# PenguinPi.net
KiCad netlist of a schematic drawn in Altium Designer
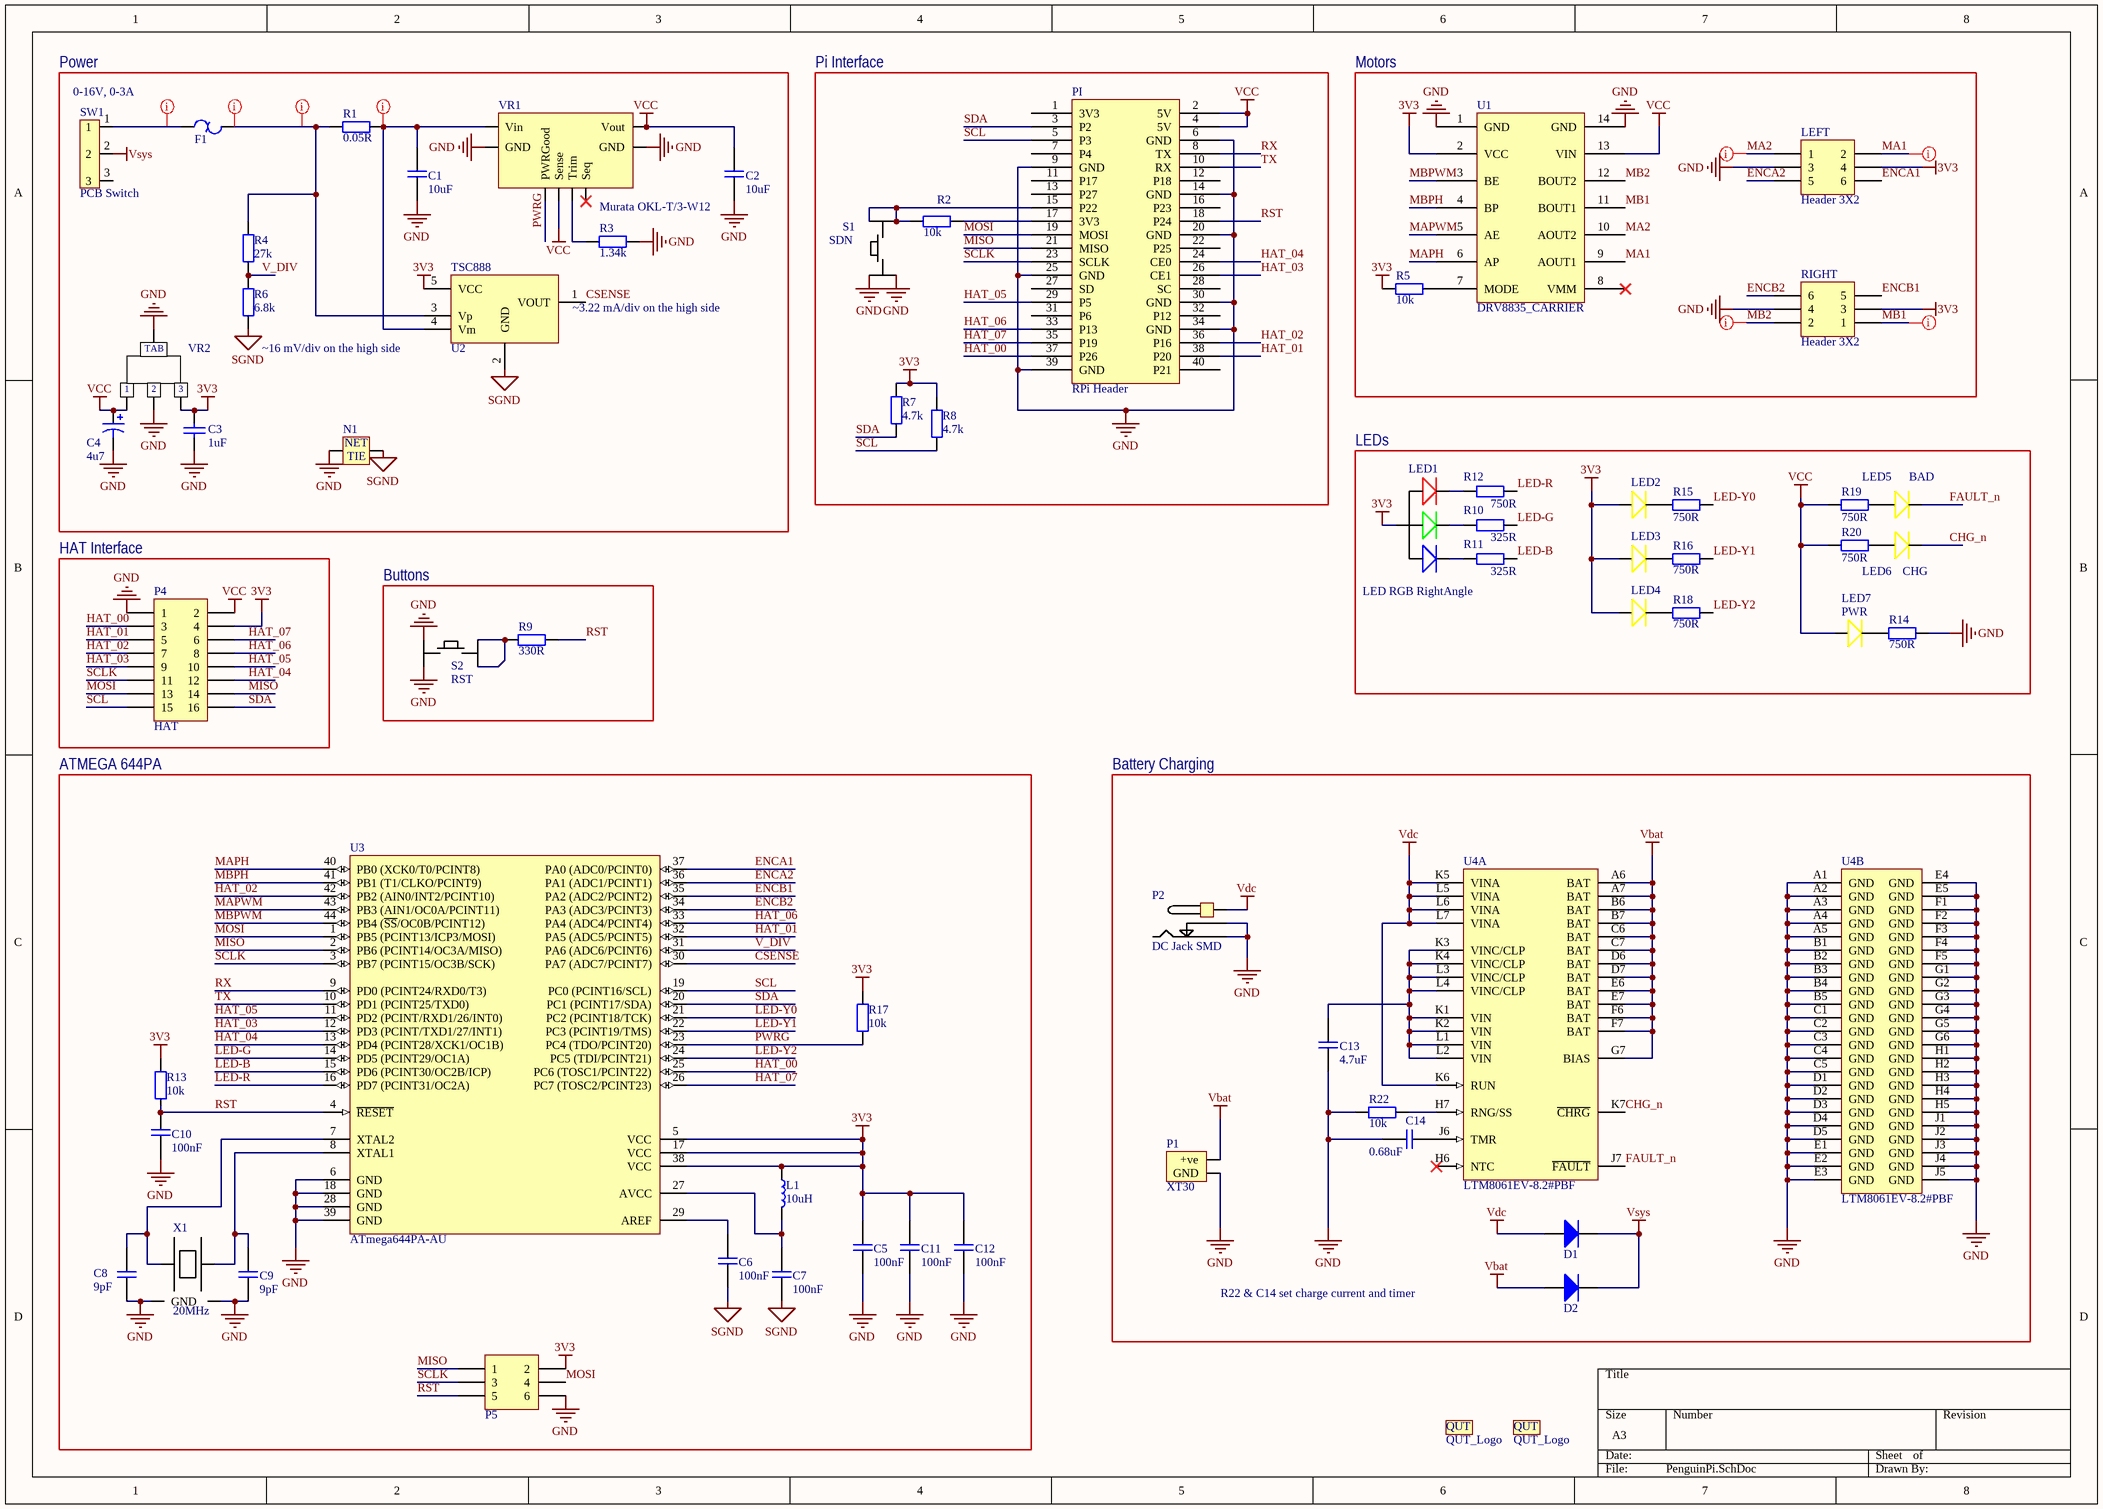
[diagram p0: PenguinPi.SchDoc]

(export (version "E")
  (design (tool "Eeschema 10.0.6"))
  (components
    (comp (ref "C1")
      (value "10uF")
      (footprint "CAPC2012X07N")
      (description "Surface mount capacitor")
      (fields (field (name "Comment") "CAP SMD"))
      (libsource (lib "Penguin") (part "CAP SMD"))
    )
    (comp (ref "C2")
      (value "10uF")
      (footprint "CAPC2012X07N")
      (description "Surface mount capacitor")
      (fields (field (name "Comment") "CAP SMD"))
      (libsource (lib "Penguin") (part "CAP SMD"))
    )
    (comp (ref "C3")
      (value "1uF")
      (footprint "6-0805_M")
      (description "Capacitor")
      (fields (field (name "Comment") "Cap") (field (name "PUBLISHER") "Altium Limited"))
      (libsource (lib "Miscellaneous Devices") (part "Cap"))
    )
    (comp (ref "C4")
      (value "4u7")
      (footprint "6-0805_M")
      (description "Polarized Capacitor (Radial)")
      (fields (field (name "Comment") "Cap Pol1") (field (name "PUBLISHER") "Altium Limited"))
      (libsource (lib "Miscellaneous Devices") (part "Cap Pol1"))
    )
    (comp (ref "C5")
      (value "100nF")
      (footprint "CAPC2012X07N")
      (description "Surface mount capacitor")
      (fields (field (name "Comment") "CAP SMD"))
      (libsource (lib "Penguin") (part "CAP SMD"))
    )
    (comp (ref "C6")
      (value "100nF")
      (footprint "CAPC2012X07N")
      (description "Surface mount capacitor")
      (fields (field (name "Comment") "CAP SMD"))
      (libsource (lib "Penguin") (part "CAP SMD"))
    )
    (comp (ref "C7")
      (value "100nF")
      (footprint "CAPC2012X07N")
      (description "Surface mount capacitor")
      (fields (field (name "Comment") "CAP SMD"))
      (libsource (lib "Penguin") (part "CAP SMD"))
    )
    (comp (ref "C8")
      (value "9pF")
      (footprint "CAPC2012X07N")
      (description "Surface mount capacitor")
      (fields (field (name "Comment") "CAP SMD"))
      (libsource (lib "Penguin") (part "CAP SMD"))
    )
    (comp (ref "C9")
      (value "9pF")
      (footprint "CAPC2012X07N")
      (description "Surface mount capacitor")
      (fields (field (name "Comment") "CAP SMD"))
      (libsource (lib "Penguin") (part "CAP SMD"))
    )
    (comp (ref "C10")
      (value "100nF")
      (footprint "CAPC2012X07N")
      (description "Surface mount capacitor")
      (fields (field (name "Comment") "CAP SMD"))
      (libsource (lib "Penguin") (part "CAP SMD"))
    )
    (comp (ref "C11")
      (value "100nF")
      (footprint "CAPC2012X07N")
      (description "Surface mount capacitor")
      (fields (field (name "Comment") "CAP SMD"))
      (libsource (lib "Penguin") (part "CAP SMD"))
    )
    (comp (ref "C12")
      (value "100nF")
      (footprint "CAPC2012X07N")
      (description "Surface mount capacitor")
      (fields (field (name "Comment") "CAP SMD"))
      (libsource (lib "Penguin") (part "CAP SMD"))
    )
    (comp (ref "C13")
      (value "4.7uF")
      (footprint "CAPC2012X07N")
      (description "Surface mount capacitor")
      (fields (field (name "Comment") "CAP SMD"))
      (libsource (lib "Penguin") (part "CAP SMD"))
    )
    (comp (ref "C14")
      (value "0.68uF")
      (footprint "CAPC2012X07N")
      (description "Surface mount capacitor")
      (fields (field (name "Comment") "CAP SMD"))
      (libsource (lib "Penguin") (part "CAP SMD"))
    )
    (comp (ref "D1")
      (value "SMD DIODE")
      (footprint "SODFL470X110-2N")
      (description "Surface mount Diode")
      (libsource (lib "Penguin") (part "SMD DIODE"))
    )
    (comp (ref "D2")
      (value "SMD DIODE")
      (footprint "SODFL470X110-2N")
      (description "Surface mount Diode")
      (libsource (lib "Penguin") (part "SMD DIODE"))
    )
    (comp (ref "F1")
      (value "RGEF250")
      (footprint "MF-MSMF250/16X-2")
      (description "PPTC Thermal Fuse")
      (libsource (lib "Penguin") (part "RGEF250"))
    )
    (comp (ref "L1")
      (value "10uH")
      (footprint "CM322522")
      (description "Surface Mount Inductor - varying sizes")
      (fields (field (name "Comment") "INDUCTOR SMD"))
      (libsource (lib "Penguin") (part "INDUCTOR SMD"))
    )
    (comp (ref "LED1")
      (value "LED RGB RightAngle")
      (footprint "LED RGB RightAngle")
      (libsource (lib "PenguinPi_v2") (part "LED RGB RightAngle"))
    )
    (comp (ref "LED2")
      (value "~")
      (footprint "LED YELLOW RightAngle")
      (libsource (lib "PenguinPi_v2") (part "LED Yellow RightAngle"))
    )
    (comp (ref "LED3")
      (value "~")
      (footprint "LED YELLOW RightAngle")
      (libsource (lib "PenguinPi_v2") (part "LED Yellow RightAngle"))
    )
    (comp (ref "LED4")
      (value "~")
      (footprint "LED YELLOW RightAngle")
      (libsource (lib "PenguinPi_v2") (part "LED Yellow RightAngle"))
    )
    (comp (ref "LED5")
      (value "BAD")
      (footprint "RESC2012X07N")
      (libsource (lib "PenguinPi_v2") (part "LED Yellow RightAngle"))
    )
    (comp (ref "LED6")
      (value "CHG")
      (footprint "RESC2012X07N")
      (libsource (lib "PenguinPi_v2") (part "LED Yellow RightAngle"))
    )
    (comp (ref "LED7")
      (value "PWR")
      (footprint "LED YELLOW RightAngle")
      (libsource (lib "PenguinPi_v2") (part "LED Yellow RightAngle"))
    )
    (comp (ref "LEFT")
      (value "Header 3X2")
      (footprint "HDR2X3")
      (description "Header, 3-Pin, Dual row")
      (fields (field (name "PUBLISHER") "Altium Limited"))
      (libsource (lib "") (part "Header 3X2_1"))
    )
    (comp (ref "LG1") (value "QUT_Logo") (footprint "QUT_Logo") (libsource (lib "Penguin") (part "QUT_Logo")))
    (comp (ref "LG2") (value "QUT_Logo") (footprint "QUT_Logo") (libsource (lib "Penguin") (part "QUT_Logo")))
    (comp (ref "N1")
      (value "NETTIE")
      (footprint "NETTIE-SMD-5mil")
      (libsource (lib "Penguin") (part "NETTIE"))
    )
    (comp (ref "P1") (value "XT30") (footprint "XT30 - PCB mount") (libsource (lib "QUT") (part "XT30")))
    (comp (ref "P2")
      (value "DC Jack SMD")
      (footprint "DC Jack SMD")
      (libsource (lib "QUT") (part "DC Jack SMD"))
    )
    (comp (ref "P4")
      (value "HAT")
      (footprint "HDR2X8")
      (description "Header, 8-Pin, Dual row")
      (fields (field (name "PUBLISHER") "Altium Limited"))
      (libsource (lib "Miscellaneous Connectors") (part "Header 8X2"))
    )
    (comp (ref "P5")
      (value "ISP")
      (footprint "Header 3x2 nonstandard")
      (description "3 by 2 header, staggered pin arrangement")
      (libsource (lib "Penguin") (part "Header 3x2 Staggered"))
    )
    (comp (ref "PI")
      (value "RPi Header")
      (footprint "RPI 2 Header")
      (description "GPIO connector for Raspberry Pi Microcomputer")
      (libsource (lib "Penguin") (part "RPi 2 Header"))
    )
    (comp (ref "R1")
      (value "0.05R")
      (footprint "RESC3216X06M")
      (description "0805 surface mount resistor")
      (fields (field (name "Comment") "RES SMD"))
      (libsource (lib "") (part "RES SMD_3"))
    )
    (comp (ref "R2")
      (value "10k")
      (footprint "RESC2012X07N")
      (description "0805 surface mount resistor")
      (fields (field (name "Comment") "RES SMD"))
      (libsource (lib "Penguin") (part "RES SMD"))
    )
    (comp (ref "R3")
      (value "1.34k")
      (footprint "RESC2012X07N")
      (description "0805 surface mount resistor")
      (fields (field (name "Comment") "RES SMD"))
      (libsource (lib "") (part "RES SMD_2"))
    )
    (comp (ref "R4")
      (value "27k")
      (footprint "RESC2012X07N")
      (description "0805 surface mount resistor")
      (fields (field (name "Comment") "RES SMD"))
      (libsource (lib "") (part "RES SMD_1"))
    )
    (comp (ref "R5")
      (value "10k")
      (footprint "RESC2012X07N")
      (description "0805 surface mount resistor")
      (fields (field (name "Comment") "RES SMD"))
      (libsource (lib "Penguin") (part "RES SMD"))
    )
    (comp (ref "R6")
      (value "6.8k")
      (footprint "RESC2012X07N")
      (description "0805 surface mount resistor")
      (fields (field (name "Comment") "RES SMD"))
      (libsource (lib "") (part "RES SMD_1"))
    )
    (comp (ref "R7")
      (value "4.7k")
      (footprint "RESC2012X07N")
      (description "0805 surface mount resistor")
      (fields (field (name "Comment") "RES SMD"))
      (libsource (lib "") (part "RES SMD_1"))
    )
    (comp (ref "R8")
      (value "4.7k")
      (footprint "RESC2012X07N")
      (description "0805 surface mount resistor")
      (fields (field (name "Comment") "RES SMD"))
      (libsource (lib "") (part "RES SMD_1"))
    )
    (comp (ref "R9")
      (value "330R")
      (footprint "RESC2012X07N")
      (description "0805 surface mount resistor")
      (fields (field (name "Comment") "RES SMD"))
      (libsource (lib "Penguin") (part "RES SMD"))
    )
    (comp (ref "R10")
      (value "325R")
      (footprint "RESC2012X07N")
      (description "0805 surface mount resistor")
      (fields (field (name "Comment") "RES SMD"))
      (libsource (lib "Penguin") (part "RES SMD"))
    )
    (comp (ref "R11")
      (value "325R")
      (footprint "RESC2012X07N")
      (description "0805 surface mount resistor")
      (fields (field (name "Comment") "RES SMD"))
      (libsource (lib "Penguin") (part "RES SMD"))
    )
    (comp (ref "R12")
      (value "750R")
      (footprint "RESC2012X07N")
      (description "0805 surface mount resistor")
      (fields (field (name "Comment") "RES SMD"))
      (libsource (lib "Penguin") (part "RES SMD"))
    )
    (comp (ref "R13")
      (value "10k")
      (footprint "RESC2012X07N")
      (description "0805 surface mount resistor")
      (fields (field (name "Comment") "RES SMD"))
      (libsource (lib "") (part "RES SMD_1"))
    )
    (comp (ref "R14")
      (value "750R")
      (footprint "RESC2012X07N")
      (description "0805 surface mount resistor")
      (fields (field (name "Comment") "RES SMD"))
      (libsource (lib "Penguin") (part "RES SMD"))
    )
    (comp (ref "R15")
      (value "750R")
      (footprint "RESC2012X07N")
      (description "0805 surface mount resistor")
      (fields (field (name "Comment") "RES SMD"))
      (libsource (lib "Penguin") (part "RES SMD"))
    )
    (comp (ref "R16")
      (value "750R")
      (footprint "RESC2012X07N")
      (description "0805 surface mount resistor")
      (fields (field (name "Comment") "RES SMD"))
      (libsource (lib "Penguin") (part "RES SMD"))
    )
    (comp (ref "R17")
      (value "10k")
      (footprint "RESC2012X07N")
      (description "0805 surface mount resistor")
      (fields (field (name "Comment") "RES SMD"))
      (libsource (lib "") (part "RES SMD_1"))
    )
    (comp (ref "R18")
      (value "750R")
      (footprint "RESC2012X07N")
      (description "0805 surface mount resistor")
      (fields (field (name "Comment") "RES SMD"))
      (libsource (lib "Penguin") (part "RES SMD"))
    )
    (comp (ref "R19")
      (value "750R")
      (footprint "6-0805_M")
      (description "0805 surface mount resistor")
      (fields (field (name "Comment") "RES SMD"))
      (libsource (lib "Penguin") (part "RES SMD"))
    )
    (comp (ref "R20")
      (value "750R")
      (footprint "6-0805_M")
      (description "0805 surface mount resistor")
      (fields (field (name "Comment") "RES SMD"))
      (libsource (lib "Penguin") (part "RES SMD"))
    )
    (comp (ref "R22")
      (value "10k")
      (footprint "RESC2012X07N")
      (description "0805 surface mount resistor")
      (fields (field (name "Comment") "RES SMD"))
      (libsource (lib "") (part "RES SMD_2"))
    )
    (comp (ref "RIGHT")
      (value "Header 3X2")
      (footprint "HDR2X3")
      (description "Header, 3-Pin, Dual row")
      (fields (field (name "PUBLISHER") "Altium Limited"))
      (libsource (lib "Miscellaneous Connectors") (part "Header 3X2"))
    )
    (comp (ref "S1")
      (value "SDN")
      (footprint "E-SWITCH-TL3342")
      (description "TL 3342 surface mount pushbutton")
      (libsource (lib "Penguin") (part "E-SWITCH-PUSHBUTTON"))
    )
    (comp (ref "S2")
      (value "RST")
      (footprint "E-SWITCH-TL3342")
      (description "TL 3342 surface mount pushbutton")
      (libsource (lib "Penguin") (part "E-SWITCH-PUSHBUTTON"))
    )
    (comp (ref "SW1")
      (value "PCB Switch")
      (footprint "PCB Switch")
      (libsource (lib "PenguinPi_v2") (part "PCB Switch"))
    )
    (comp (ref "U1")
      (value "DRV8835_CARRIER")
      (footprint "DRV8835_CARRIER")
      (description "DRV8835 Motor Controller")
      (libsource (lib "Penguin") (part "DRV8835_CARRIER"))
    )
    (comp (ref "U2")
      (value "TSC888")
      (footprint "SOT95P280X145-5N")
      (description "Curent Sense Amplifier")
      (libsource (lib "Penguin") (part "TSC888"))
    )
    (comp (ref "U3")
      (value "ATmega644PA-AU")
      (footprint "44A_L")
      (libsource (lib "Altium Content Vault") (part "MC-8B-ATM128-SQ44"))
    )
    (comp (ref "U4")
      (value "LTM8061EV-8.2#PBF")
      (footprint "LT-LGA-77-05-08-1856_V")
      (description "32 V, 2 A uModule Li-Ion / Polymer Battery Charger, 77-pin LGA, -40 to 125 degC, Pb-Free, Tray")
      (fields (field (name "MANUFACTURER") "Linear Technology"))
      (libsource (lib "Altium Content Vault") (part "CMP-0483-00150-1"))
    )
    (comp (ref "VR1")
      (value "Murata OKL-T/3-W12")
      (footprint "OKL-T/3-W12")
      (libsource (lib "PenguinPi_v2") (part "Murata OKL-T/3-W12"))
    )
    (comp (ref "VR2") (value "FT_SOT223") (footprint "SOT233-4N") (libsource (lib "QUT") (part "FT_SOT223")))
    (comp (ref "X1") (value "20MHz") (footprint "XTAL TSX3225") (libsource (lib "QUT") (part "XTAL ABM3B")))
  )
  (nets
    (net (code "1") (name "/CHG_n") (class "Default")
      (node (ref "LED6") (pin "1") (pinfunction "YELLOW_1") (pintype "passive"))
      (node (ref "U4") (pin "K7") (pinfunction "~{CHRG}_K7") (pintype "tri_state"))
    )
    (net (code "2") (name "/CSENSE") (class "Default")
      (node (ref "U2") (pin "1") (pinfunction "VOUT_1") (pintype "passive"))
      (node (ref "U3") (pin "30") (pinfunction "PA7_(ADC7/PCINT7)_30") (pintype "bidirectional"))
    )
    (net (code "3") (name "/ENCA1") (class "Default")
      (node (ref "LEFT") (pin "6") (pinfunction "6_6") (pintype "passive"))
      (node (ref "U3") (pin "37") (pinfunction "PA0_(ADC0/PCINT0)_37") (pintype "bidirectional"))
    )
    (net (code "4") (name "/ENCA2") (class "Default")
      (node (ref "LEFT") (pin "5") (pinfunction "5_5") (pintype "passive"))
      (node (ref "U3") (pin "36") (pinfunction "PA1_(ADC1/PCINT1)_36") (pintype "bidirectional"))
    )
    (net (code "5") (name "/ENCB1") (class "Default")
      (node (ref "RIGHT") (pin "5") (pinfunction "5_5") (pintype "passive"))
      (node (ref "U3") (pin "35") (pinfunction "PA2_(ADC2/PCINT2)_35") (pintype "bidirectional"))
    )
    (net (code "6") (name "/ENCB2") (class "Default")
      (node (ref "RIGHT") (pin "6") (pinfunction "6_6") (pintype "passive"))
      (node (ref "U3") (pin "34") (pinfunction "PA3_(ADC3/PCINT3)_34") (pintype "bidirectional"))
    )
    (net (code "7") (name "/FAULT_n") (class "Default")
      (node (ref "LED5") (pin "1") (pinfunction "YELLOW_1") (pintype "passive"))
      (node (ref "U4") (pin "J7") (pinfunction "~{FAULT}_J7") (pintype "tri_state"))
    )
    (net (code "8") (name "/HAT_00") (class "Default")
      (node (ref "P4") (pin "3") (pinfunction "3_3") (pintype "passive"))
      (node (ref "PI") (pin "37") (pinfunction "P26_37") (pintype "passive"))
      (node (ref "U3") (pin "25") (pinfunction "PC6_(TOSC1/PCINT22)_25") (pintype "bidirectional"))
    )
    (net (code "9") (name "/HAT_01") (class "Default")
      (node (ref "P4") (pin "5") (pinfunction "5_5") (pintype "passive"))
      (node (ref "PI") (pin "38") (pinfunction "P20_38") (pintype "passive"))
      (node (ref "U3") (pin "32") (pinfunction "PA5_(ADC5/PCINT5)_32") (pintype "bidirectional"))
    )
    (net (code "10") (name "/HAT_02") (class "Default")
      (node (ref "P4") (pin "7") (pinfunction "7_7") (pintype "passive"))
      (node (ref "PI") (pin "36") (pinfunction "P16_36") (pintype "passive"))
      (node (ref "U3") (pin "42") (pinfunction "PB2_(AIN0/INT2/PCINT10)_42") (pintype "bidirectional"))
    )
    (net (code "11") (name "/HAT_03") (class "Default")
      (node (ref "P4") (pin "9") (pinfunction "9_9") (pintype "passive"))
      (node (ref "PI") (pin "26") (pinfunction "CE1_26") (pintype "passive"))
      (node (ref "U3") (pin "12") (pinfunction "PD3_(PCINT/TXD1/27/INT1)_12") (pintype "bidirectional"))
    )
    (net (code "12") (name "/HAT_04") (class "Default")
      (node (ref "P4") (pin "12") (pinfunction "12_12") (pintype "passive"))
      (node (ref "PI") (pin "24") (pinfunction "CE0_24") (pintype "passive"))
      (node (ref "U3") (pin "13") (pinfunction "PD4_(PCINT28/XCK1/OC1B)_13") (pintype "bidirectional"))
    )
    (net (code "13") (name "/HAT_05") (class "Default")
      (node (ref "P4") (pin "10") (pinfunction "10_10") (pintype "passive"))
      (node (ref "PI") (pin "29") (pinfunction "P5_29") (pintype "passive"))
      (node (ref "U3") (pin "11") (pinfunction "PD2_(PCINT/RXD1/26/INT0)_11") (pintype "bidirectional"))
    )
    (net (code "14") (name "/HAT_06") (class "Default")
      (node (ref "P4") (pin "8") (pinfunction "8_8") (pintype "passive"))
      (node (ref "PI") (pin "33") (pinfunction "P13_33") (pintype "passive"))
      (node (ref "U3") (pin "33") (pinfunction "PA4_(ADC4/PCINT4)_33") (pintype "bidirectional"))
    )
    (net (code "15") (name "/HAT_07") (class "Default")
      (node (ref "P4") (pin "6") (pinfunction "6_6") (pintype "passive"))
      (node (ref "PI") (pin "35") (pinfunction "P19_35") (pintype "passive"))
      (node (ref "U3") (pin "26") (pinfunction "PC7_(TOSC2/PCINT23)_26") (pintype "bidirectional"))
    )
    (net (code "16") (name "/LED-B") (class "Default")
      (node (ref "R11") (pin "2") (pinfunction "2_2") (pintype "passive"))
      (node (ref "U3") (pin "15") (pinfunction "PD6_(PCINT30/OC2B/ICP)_15") (pintype "bidirectional"))
    )
    (net (code "17") (name "/LED-G") (class "Default")
      (node (ref "R10") (pin "2") (pinfunction "2_2") (pintype "passive"))
      (node (ref "U3") (pin "14") (pinfunction "PD5_(PCINT29/OC1A)_14") (pintype "bidirectional"))
    )
    (net (code "18") (name "/LED-R") (class "Default")
      (node (ref "R12") (pin "2") (pinfunction "2_2") (pintype "passive"))
      (node (ref "U3") (pin "16") (pinfunction "PD7_(PCINT31/OC2A)_16") (pintype "bidirectional"))
    )
    (net (code "19") (name "/LED-Y0") (class "Default")
      (node (ref "R15") (pin "2") (pinfunction "2_2") (pintype "passive"))
      (node (ref "U3") (pin "21") (pinfunction "PC2_(PCINT18/TCK)_21") (pintype "bidirectional"))
    )
    (net (code "20") (name "/LED-Y1") (class "Default")
      (node (ref "R16") (pin "2") (pinfunction "2_2") (pintype "passive"))
      (node (ref "U3") (pin "22") (pinfunction "PC3_(PCINT19/TMS)_22") (pintype "bidirectional"))
    )
    (net (code "21") (name "/LED-Y2") (class "Default")
      (node (ref "R18") (pin "2") (pinfunction "2_2") (pintype "passive"))
      (node (ref "U3") (pin "24") (pinfunction "PC5_(TDI/PCINT21)_24") (pintype "bidirectional"))
    )
    (net (code "22") (name "/MA1") (class "Default")
      (node (ref "LEFT") (pin "2") (pinfunction "2_2") (pintype "passive"))
      (node (ref "U1") (pin "9") (pinfunction "AOUT1_9") (pintype "passive"))
    )
    (net (code "23") (name "/MA2") (class "Default")
      (node (ref "LEFT") (pin "1") (pinfunction "1_1") (pintype "passive"))
      (node (ref "U1") (pin "10") (pinfunction "AOUT2_10") (pintype "passive"))
    )
    (net (code "24") (name "/MAPH") (class "Default")
      (node (ref "U1") (pin "6") (pinfunction "AP_6") (pintype "passive"))
      (node (ref "U3") (pin "40") (pinfunction "PB0_(XCK0/T0/PCINT8)_40") (pintype "bidirectional"))
    )
    (net (code "25") (name "/MAPWM") (class "Default")
      (node (ref "U1") (pin "5") (pinfunction "AE_5") (pintype "passive"))
      (node (ref "U3") (pin "43") (pinfunction "PB3_(AIN1/OC0A/PCINT11)_43") (pintype "bidirectional"))
    )
    (net (code "26") (name "/MB1") (class "Default")
      (node (ref "RIGHT") (pin "1") (pinfunction "1_1") (pintype "passive"))
      (node (ref "U1") (pin "11") (pinfunction "BOUT1_11") (pintype "passive"))
    )
    (net (code "27") (name "/MB2") (class "Default")
      (node (ref "RIGHT") (pin "2") (pinfunction "2_2") (pintype "passive"))
      (node (ref "U1") (pin "12") (pinfunction "BOUT2_12") (pintype "passive"))
    )
    (net (code "28") (name "/MBPH") (class "Default")
      (node (ref "U1") (pin "4") (pinfunction "BP_4") (pintype "passive"))
      (node (ref "U3") (pin "41") (pinfunction "PB1_(T1/CLKO/PCINT9)_41") (pintype "bidirectional"))
    )
    (net (code "29") (name "/MBPWM") (class "Default")
      (node (ref "U1") (pin "3") (pinfunction "BE_3") (pintype "passive"))
      (node (ref "U3") (pin "44") (pinfunction "PB4_(~{SS}/OC0B/PCINT12)_44") (pintype "bidirectional"))
    )
    (net (code "30") (name "/MISO") (class "Default")
      (node (ref "P4") (pin "14") (pinfunction "14_14") (pintype "passive"))
      (node (ref "P5") (pin "1") (pinfunction "1_1") (pintype "passive"))
      (node (ref "PI") (pin "21") (pinfunction "MISO_21") (pintype "passive"))
      (node (ref "U3") (pin "2") (pinfunction "PB6_(PCINT14/OC3A/MISO)_2") (pintype "bidirectional"))
    )
    (net (code "31") (name "/MOSI") (class "Default")
      (node (ref "P4") (pin "13") (pinfunction "13_13") (pintype "passive"))
      (node (ref "P5") (pin "4") (pinfunction "4_4") (pintype "passive"))
      (node (ref "PI") (pin "19") (pinfunction "MOSI_19") (pintype "passive"))
      (node (ref "U3") (pin "1") (pinfunction "PB5_(PCINT13/ICP3/MOSI)_1") (pintype "bidirectional"))
    )
    (net (code "32") (name "/PWRG") (class "Default")
      (node (ref "R17") (pin "1") (pinfunction "1_1") (pintype "passive"))
      (node (ref "U3") (pin "23") (pinfunction "PC4_(TDO/PCINT20)_23") (pintype "bidirectional"))
      (node (ref "VR1") (pin "10") (pinfunction "PWRGood_10") (pintype "passive"))
    )
    (net (code "33") (name "/RST") (class "Default")
      (node (ref "C10") (pin "2") (pinfunction "K_2") (pintype "passive"))
      (node (ref "P5") (pin "5") (pinfunction "5_5") (pintype "passive"))
      (node (ref "PI") (pin "18") (pinfunction "P24_18") (pintype "passive"))
      (node (ref "R13") (pin "1") (pinfunction "1_1") (pintype "passive"))
      (node (ref "R9") (pin "2") (pinfunction "2_2") (pintype "passive"))
      (node (ref "U3") (pin "4") (pinfunction "~{RESET}_4") (pintype "input"))
    )
    (net (code "34") (name "/RX") (class "Default")
      (node (ref "PI") (pin "8") (pinfunction "TX_8") (pintype "passive"))
      (node (ref "U3") (pin "9") (pinfunction "PD0_(PCINT24/RXD0/T3)_9") (pintype "bidirectional"))
    )
    (net (code "35") (name "/SCL") (class "Default")
      (node (ref "P4") (pin "15") (pinfunction "15_15") (pintype "passive"))
      (node (ref "PI") (pin "5") (pinfunction "P3_5") (pintype "passive"))
      (node (ref "R8") (pin "1") (pinfunction "1_1") (pintype "passive"))
      (node (ref "U3") (pin "19") (pinfunction "PC0_(PCINT16/SCL)_19") (pintype "bidirectional"))
    )
    (net (code "36") (name "/SCLK") (class "Default")
      (node (ref "P4") (pin "11") (pinfunction "11_11") (pintype "passive"))
      (node (ref "P5") (pin "3") (pinfunction "3_3") (pintype "passive"))
      (node (ref "PI") (pin "23") (pinfunction "SCLK_23") (pintype "passive"))
      (node (ref "U3") (pin "3") (pinfunction "PB7_(PCINT15/OC3B/SCK)_3") (pintype "bidirectional"))
    )
    (net (code "37") (name "/SDA") (class "Default")
      (node (ref "P4") (pin "16") (pinfunction "16_16") (pintype "passive"))
      (node (ref "PI") (pin "3") (pinfunction "P2_3") (pintype "passive"))
      (node (ref "R7") (pin "1") (pinfunction "1_1") (pintype "passive"))
      (node (ref "U3") (pin "20") (pinfunction "PC1_(PCINT17/SDA)_20") (pintype "bidirectional"))
    )
    (net (code "38") (name "/TX") (class "Default")
      (node (ref "PI") (pin "10") (pinfunction "RX_10") (pintype "passive"))
      (node (ref "U3") (pin "10") (pinfunction "PD1_(PCINT25/TXD0)_10") (pintype "bidirectional"))
    )
    (net (code "39") (name "/V_DIV") (class "Default")
      (node (ref "R4") (pin "1") (pinfunction "1_1") (pintype "passive"))
      (node (ref "R6") (pin "2") (pinfunction "2_2") (pintype "passive"))
      (node (ref "U3") (pin "31") (pinfunction "PA6_(ADC6/PCINT6)_31") (pintype "bidirectional"))
    )
    (net (code "40") (name "3V3") (class "Default")
      (node (ref "C11") (pin "2") (pinfunction "K_2") (pintype "passive"))
      (node (ref "C12") (pin "2") (pinfunction "K_2") (pintype "passive"))
      (node (ref "C3") (pin "2") (pinfunction "2_2") (pintype "passive"))
      (node (ref "C5") (pin "2") (pinfunction "K_2") (pintype "passive"))
      (node (ref "L1") (pin "1") (pinfunction "Anode_1") (pintype "passive"))
      (node (ref "LED1") (pin "2") (pinfunction "ANODE_2") (pintype "passive"))
      (node (ref "LED2") (pin "2") (pinfunction "ANODE_2") (pintype "passive"))
      (node (ref "LED3") (pin "2") (pinfunction "ANODE_2") (pintype "passive"))
      (node (ref "LED4") (pin "2") (pinfunction "ANODE_2") (pintype "passive"))
      (node (ref "LEFT") (pin "4") (pinfunction "4_4") (pintype "passive"))
      (node (ref "P4") (pin "4") (pinfunction "4_4") (pintype "passive"))
      (node (ref "P5") (pin "2") (pinfunction "2_2") (pintype "passive"))
      (node (ref "R13") (pin "2") (pinfunction "2_2") (pintype "passive"))
      (node (ref "R17") (pin "2") (pinfunction "2_2") (pintype "passive"))
      (node (ref "R5") (pin "1") (pinfunction "1_1") (pintype "passive"))
      (node (ref "R7") (pin "2") (pinfunction "2_2") (pintype "passive"))
      (node (ref "R8") (pin "2") (pinfunction "2_2") (pintype "passive"))
      (node (ref "RIGHT") (pin "3") (pinfunction "3_3") (pintype "passive"))
      (node (ref "U1") (pin "2") (pinfunction "VCC_2") (pintype "passive"))
      (node (ref "U2") (pin "5") (pinfunction "VCC_5") (pintype "passive"))
      (node (ref "U3") (pin "17") (pinfunction "VCC_17") (pintype "power_in"))
      (node (ref "U3") (pin "38") (pinfunction "VCC_38") (pintype "power_in"))
      (node (ref "U3") (pin "5") (pinfunction "VCC_5") (pintype "power_in"))
      (node (ref "VR2") (pin "3") (pinfunction "3_3") (pintype "passive"))
    )
    (net (code "41") (name "GND") (class "Default")
      (node (ref "C1") (pin "1") (pinfunction "A_1") (pintype "passive"))
      (node (ref "C10") (pin "1") (pinfunction "A_1") (pintype "passive"))
      (node (ref "C11") (pin "1") (pinfunction "A_1") (pintype "passive"))
      (node (ref "C12") (pin "1") (pinfunction "A_1") (pintype "passive"))
      (node (ref "C13") (pin "1") (pinfunction "A_1") (pintype "passive"))
      (node (ref "C14") (pin "2") (pinfunction "K_2") (pintype "passive"))
      (node (ref "C2") (pin "1") (pinfunction "A_1") (pintype "passive"))
      (node (ref "C3") (pin "1") (pinfunction "1_1") (pintype "passive"))
      (node (ref "C4") (pin "2") (pinfunction "2_2") (pintype "passive"))
      (node (ref "C5") (pin "1") (pinfunction "A_1") (pintype "passive"))
      (node (ref "C8") (pin "1") (pinfunction "A_1") (pintype "passive"))
      (node (ref "C9") (pin "1") (pinfunction "A_1") (pintype "passive"))
      (node (ref "LEFT") (pin "3") (pinfunction "3_3") (pintype "passive"))
      (node (ref "N1") (pin "1") (pinfunction "1_1") (pintype "passive"))
      (node (ref "P1") (pin "1") (pinfunction "GND_1") (pintype "passive"))
      (node (ref "P2") (pin "2") (pinfunction "2_2") (pintype "passive"))
      (node (ref "P2") (pin "3") (pinfunction "3_3") (pintype "passive"))
      (node (ref "P4") (pin "1") (pinfunction "1_1") (pintype "passive"))
      (node (ref "P5") (pin "6") (pinfunction "6_6") (pintype "passive"))
      (node (ref "PI") (pin "14") (pinfunction "GND_14") (pintype "passive"))
      (node (ref "PI") (pin "20") (pinfunction "GND_20") (pintype "passive"))
      (node (ref "PI") (pin "25") (pinfunction "GND_25") (pintype "passive"))
      (node (ref "PI") (pin "30") (pinfunction "GND_30") (pintype "passive"))
      (node (ref "PI") (pin "34") (pinfunction "GND_34") (pintype "passive"))
      (node (ref "PI") (pin "39") (pinfunction "GND_39") (pintype "passive"))
      (node (ref "PI") (pin "6") (pinfunction "GND_6") (pintype "passive"))
      (node (ref "PI") (pin "9") (pinfunction "GND_9") (pintype "passive"))
      (node (ref "R14") (pin "2") (pinfunction "2_2") (pintype "passive"))
      (node (ref "R22") (pin "2") (pinfunction "2_2") (pintype "passive"))
      (node (ref "R3") (pin "1") (pinfunction "1_1") (pintype "passive"))
      (node (ref "RIGHT") (pin "4") (pinfunction "4_4") (pintype "passive"))
      (node (ref "S1") (pin "3") (pinfunction "B'_3") (pintype "passive"))
      (node (ref "S1") (pin "4") (pinfunction "B_4") (pintype "passive"))
      (node (ref "S2") (pin "1") (pinfunction "A_1") (pintype "passive"))
      (node (ref "S2") (pin "2") (pinfunction "A'_2") (pintype "passive"))
      (node (ref "U1") (pin "1") (pinfunction "GND_1") (pintype "passive"))
      (node (ref "U1") (pin "14") (pinfunction "GND_14") (pintype "passive"))
      (node (ref "U3") (pin "18") (pinfunction "GND_18") (pintype "power_in"))
      (node (ref "U3") (pin "28") (pinfunction "GND_28") (pintype "power_in"))
      (node (ref "U3") (pin "39") (pinfunction "GND_39") (pintype "power_in"))
      (node (ref "U3") (pin "6") (pinfunction "GND_6") (pintype "power_in"))
      (node (ref "U4") (pin "A1") (pinfunction "GND_A1") (pintype "power_in"))
      (node (ref "U4") (pin "A2") (pinfunction "GND_A2") (pintype "power_in"))
      (node (ref "U4") (pin "A3") (pinfunction "GND_A3") (pintype "power_in"))
      (node (ref "U4") (pin "A4") (pinfunction "GND_A4") (pintype "power_in"))
      (node (ref "U4") (pin "A5") (pinfunction "GND_A5") (pintype "power_in"))
      (node (ref "U4") (pin "B1") (pinfunction "GND_B1") (pintype "power_in"))
      (node (ref "U4") (pin "B2") (pinfunction "GND_B2") (pintype "power_in"))
      (node (ref "U4") (pin "B3") (pinfunction "GND_B3") (pintype "power_in"))
      (node (ref "U4") (pin "B4") (pinfunction "GND_B4") (pintype "power_in"))
      (node (ref "U4") (pin "B5") (pinfunction "GND_B5") (pintype "power_in"))
      (node (ref "U4") (pin "C1") (pinfunction "GND_C1") (pintype "power_in"))
      (node (ref "U4") (pin "C2") (pinfunction "GND_C2") (pintype "power_in"))
      (node (ref "U4") (pin "C3") (pinfunction "GND_C3") (pintype "power_in"))
      (node (ref "U4") (pin "C4") (pinfunction "GND_C4") (pintype "power_in"))
      (node (ref "U4") (pin "C5") (pinfunction "GND_C5") (pintype "power_in"))
      (node (ref "U4") (pin "D1") (pinfunction "GND_D1") (pintype "power_in"))
      (node (ref "U4") (pin "D2") (pinfunction "GND_D2") (pintype "power_in"))
      (node (ref "U4") (pin "D3") (pinfunction "GND_D3") (pintype "power_in"))
      (node (ref "U4") (pin "D4") (pinfunction "GND_D4") (pintype "power_in"))
      (node (ref "U4") (pin "D5") (pinfunction "GND_D5") (pintype "power_in"))
      (node (ref "U4") (pin "E1") (pinfunction "GND_E1") (pintype "power_in"))
      (node (ref "U4") (pin "E2") (pinfunction "GND_E2") (pintype "power_in"))
      (node (ref "U4") (pin "E3") (pinfunction "GND_E3") (pintype "power_in"))
      (node (ref "U4") (pin "E4") (pinfunction "GND_E4") (pintype "power_in"))
      (node (ref "U4") (pin "E5") (pinfunction "GND_E5") (pintype "power_in"))
      (node (ref "U4") (pin "F1") (pinfunction "GND_F1") (pintype "power_in"))
      (node (ref "U4") (pin "F2") (pinfunction "GND_F2") (pintype "power_in"))
      (node (ref "U4") (pin "F3") (pinfunction "GND_F3") (pintype "power_in"))
      (node (ref "U4") (pin "F4") (pinfunction "GND_F4") (pintype "power_in"))
      (node (ref "U4") (pin "F5") (pinfunction "GND_F5") (pintype "power_in"))
      (node (ref "U4") (pin "G1") (pinfunction "GND_G1") (pintype "power_in"))
      (node (ref "U4") (pin "G2") (pinfunction "GND_G2") (pintype "power_in"))
      (node (ref "U4") (pin "G3") (pinfunction "GND_G3") (pintype "power_in"))
      (node (ref "U4") (pin "G4") (pinfunction "GND_G4") (pintype "power_in"))
      (node (ref "U4") (pin "G5") (pinfunction "GND_G5") (pintype "power_in"))
      (node (ref "U4") (pin "G6") (pinfunction "GND_G6") (pintype "power_in"))
      (node (ref "U4") (pin "H1") (pinfunction "GND_H1") (pintype "power_in"))
      (node (ref "U4") (pin "H2") (pinfunction "GND_H2") (pintype "power_in"))
      (node (ref "U4") (pin "H3") (pinfunction "GND_H3") (pintype "power_in"))
      (node (ref "U4") (pin "H4") (pinfunction "GND_H4") (pintype "power_in"))
      (node (ref "U4") (pin "H5") (pinfunction "GND_H5") (pintype "power_in"))
      (node (ref "U4") (pin "J1") (pinfunction "GND_J1") (pintype "power_in"))
      (node (ref "U4") (pin "J2") (pinfunction "GND_J2") (pintype "power_in"))
      (node (ref "U4") (pin "J3") (pinfunction "GND_J3") (pintype "power_in"))
      (node (ref "U4") (pin "J4") (pinfunction "GND_J4") (pintype "power_in"))
      (node (ref "U4") (pin "J5") (pinfunction "GND_J5") (pintype "power_in"))
      (node (ref "VR1") (pin "3") (pinfunction "GND_3") (pintype "passive"))
      (node (ref "VR1") (pin "7") (pinfunction "GND_7") (pintype "passive"))
      (node (ref "VR2") (pin "2") (pinfunction "2_2") (pintype "passive"))
      (node (ref "VR2") (pin "4") (pinfunction "4_4") (pintype "passive"))
      (node (ref "X1") (pin "2") (pinfunction "GND_2") (pintype "passive"))
      (node (ref "X1") (pin "4") (pinfunction "GND_4") (pintype "passive"))
    )
    (net (code "42") (name "Net-(C1-K)") (class "Default")
      (node (ref "C1") (pin "2") (pinfunction "K_2") (pintype "passive"))
      (node (ref "R1") (pin "2") (pinfunction "2_2") (pintype "power_in"))
      (node (ref "U2") (pin "4") (pinfunction "Vm_4") (pintype "passive"))
      (node (ref "VR1") (pin "2") (pinfunction "Vin_2") (pintype "passive"))
    )
    (net (code "43") (name "Net-(C6-K)") (class "Default")
      (node (ref "C6") (pin "2") (pinfunction "K_2") (pintype "passive"))
      (node (ref "U3") (pin "29") (pinfunction "AREF_29") (pintype "power_in"))
    )
    (net (code "44") (name "Net-(C7-K)") (class "Default")
      (node (ref "C7") (pin "2") (pinfunction "K_2") (pintype "passive"))
      (node (ref "L1") (pin "2") (pinfunction "Cathode_2") (pintype "passive"))
      (node (ref "U3") (pin "27") (pinfunction "AVCC_27") (pintype "power_in"))
    )
    (net (code "45") (name "Net-(C8-K)") (class "Default")
      (node (ref "C8") (pin "2") (pinfunction "K_2") (pintype "passive"))
      (node (ref "U3") (pin "7") (pinfunction "XTAL2_7") (pintype "passive"))
      (node (ref "X1") (pin "3") (pinfunction "3_3") (pintype "passive"))
    )
    (net (code "46") (name "Net-(C9-K)") (class "Default")
      (node (ref "C9") (pin "2") (pinfunction "K_2") (pintype "passive"))
      (node (ref "U3") (pin "8") (pinfunction "XTAL1_8") (pintype "passive"))
      (node (ref "X1") (pin "1") (pinfunction "1_1") (pintype "passive"))
    )
    (net (code "47") (name "Net-(C13-K)") (class "Default")
      (node (ref "C13") (pin "2") (pinfunction "K_2") (pintype "passive"))
      (node (ref "U4") (pin "K1") (pinfunction "VIN_K1") (pintype "power_in"))
      (node (ref "U4") (pin "K2") (pinfunction "VIN_K2") (pintype "power_in"))
      (node (ref "U4") (pin "K3") (pinfunction "VINC/CLP_K3") (pintype "power_in"))
      (node (ref "U4") (pin "K4") (pinfunction "VINC/CLP_K4") (pintype "power_in"))
      (node (ref "U4") (pin "L1") (pinfunction "VIN_L1") (pintype "power_in"))
      (node (ref "U4") (pin "L2") (pinfunction "VIN_L2") (pintype "power_in"))
      (node (ref "U4") (pin "L3") (pinfunction "VINC/CLP_L3") (pintype "power_in"))
      (node (ref "U4") (pin "L4") (pinfunction "VINC/CLP_L4") (pintype "power_in"))
    )
    (net (code "48") (name "Net-(C14-A)") (class "Default")
      (node (ref "C14") (pin "1") (pinfunction "A_1") (pintype "passive"))
      (node (ref "U4") (pin "J6") (pinfunction "TMR_J6") (pintype "input"))
    )
    (net (code "49") (name "Net-(F1-Pad1)") (class "Default")
      (node (ref "F1") (pin "1") (pinfunction "1_1") (pintype "power_in"))
      (node (ref "SW1") (pin "1") (pinfunction "1_1") (pintype "passive"))
    )
    (net (code "50") (name "Net-(LED1-BLUE)") (class "Default")
      (node (ref "LED1") (pin "4") (pinfunction "BLUE_4") (pintype "passive"))
      (node (ref "R11") (pin "1") (pinfunction "1_1") (pintype "passive"))
    )
    (net (code "51") (name "Net-(LED1-GREEN)") (class "Default")
      (node (ref "LED1") (pin "3") (pinfunction "GREEN_3") (pintype "passive"))
      (node (ref "R10") (pin "1") (pinfunction "1_1") (pintype "passive"))
    )
    (net (code "52") (name "Net-(LED1-RED)") (class "Default")
      (node (ref "LED1") (pin "1") (pinfunction "RED_1") (pintype "passive"))
      (node (ref "R12") (pin "1") (pinfunction "1_1") (pintype "passive"))
    )
    (net (code "53") (name "Net-(LED2-YELLOW)") (class "Default")
      (node (ref "LED2") (pin "1") (pinfunction "YELLOW_1") (pintype "passive"))
      (node (ref "R15") (pin "1") (pinfunction "1_1") (pintype "passive"))
    )
    (net (code "54") (name "Net-(LED3-YELLOW)") (class "Default")
      (node (ref "LED3") (pin "1") (pinfunction "YELLOW_1") (pintype "passive"))
      (node (ref "R16") (pin "1") (pinfunction "1_1") (pintype "passive"))
    )
    (net (code "55") (name "Net-(LED4-YELLOW)") (class "Default")
      (node (ref "LED4") (pin "1") (pinfunction "YELLOW_1") (pintype "passive"))
      (node (ref "R18") (pin "1") (pinfunction "1_1") (pintype "passive"))
    )
    (net (code "56") (name "Net-(LED5-ANODE)") (class "Default")
      (node (ref "LED5") (pin "2") (pinfunction "ANODE_2") (pintype "passive"))
      (node (ref "R19") (pin "2") (pinfunction "2_2") (pintype "passive"))
    )
    (net (code "57") (name "Net-(LED6-ANODE)") (class "Default")
      (node (ref "LED6") (pin "2") (pinfunction "ANODE_2") (pintype "passive"))
      (node (ref "R20") (pin "2") (pinfunction "2_2") (pintype "passive"))
    )
    (net (code "58") (name "Net-(LED7-YELLOW)") (class "Default")
      (node (ref "LED7") (pin "1") (pinfunction "YELLOW_1") (pintype "passive"))
      (node (ref "R14") (pin "1") (pinfunction "1_1") (pintype "passive"))
    )
    (net (code "59") (name "Net-(PI-3V3-Pad17)") (class "Default")
      (node (ref "PI") (pin "17") (pinfunction "3V3_17") (pintype "passive"))
      (node (ref "R2") (pin "2") (pinfunction "2_2") (pintype "passive"))
    )
    (net (code "60") (name "Net-(PI-P22)") (class "Default")
      (node (ref "PI") (pin "15") (pinfunction "P22_15") (pintype "passive"))
      (node (ref "R2") (pin "1") (pinfunction "1_1") (pintype "passive"))
      (node (ref "S1") (pin "1") (pinfunction "A_1") (pintype "passive"))
      (node (ref "S1") (pin "2") (pinfunction "A'_2") (pintype "passive"))
    )
    (net (code "61") (name "Net-(S2-B')") (class "Default")
      (node (ref "R9") (pin "1") (pinfunction "1_1") (pintype "passive"))
      (node (ref "S2") (pin "3") (pinfunction "B'_3") (pintype "passive"))
      (node (ref "S2") (pin "4") (pinfunction "B_4") (pintype "passive"))
    )
    (net (code "62") (name "Net-(U1-MODE)") (class "Default")
      (node (ref "R5") (pin "2") (pinfunction "2_2") (pintype "passive"))
      (node (ref "U1") (pin "7") (pinfunction "MODE_7") (pintype "passive"))
    )
    (net (code "63") (name "Net-(U2-Vp)") (class "Default")
      (node (ref "F1") (pin "2") (pinfunction "2_2") (pintype "power_in"))
      (node (ref "R1") (pin "1") (pinfunction "1_1") (pintype "power_in"))
      (node (ref "R4") (pin "2") (pinfunction "2_2") (pintype "passive"))
      (node (ref "U2") (pin "3") (pinfunction "Vp_3") (pintype "passive"))
    )
    (net (code "64") (name "Net-(U4A-RNG{slash}SS)") (class "Default")
      (node (ref "R22") (pin "1") (pinfunction "1_1") (pintype "passive"))
      (node (ref "U4") (pin "H7") (pinfunction "RNG/SS_H7") (pintype "input"))
    )
    (net (code "65") (name "Net-(VR1-Trim)") (class "Default")
      (node (ref "R3") (pin "2") (pinfunction "2_2") (pintype "passive"))
      (node (ref "VR1") (pin "6") (pinfunction "Trim_6") (pintype "passive"))
    )
    (net (code "66") (name "SGND") (class "Default")
      (node (ref "C6") (pin "1") (pinfunction "A_1") (pintype "passive"))
      (node (ref "C7") (pin "1") (pinfunction "A_1") (pintype "passive"))
      (node (ref "N1") (pin "2") (pinfunction "2_2") (pintype "passive"))
      (node (ref "R6") (pin "1") (pinfunction "1_1") (pintype "passive"))
      (node (ref "U2") (pin "2") (pinfunction "GND_2") (pintype "passive"))
    )
    (net (code "67") (name "VCC") (class "Default")
      (node (ref "C2") (pin "2") (pinfunction "K_2") (pintype "passive"))
      (node (ref "C4") (pin "1") (pinfunction "1_1") (pintype "passive"))
      (node (ref "LED7") (pin "2") (pinfunction "ANODE_2") (pintype "passive"))
      (node (ref "P4") (pin "2") (pinfunction "2_2") (pintype "passive"))
      (node (ref "PI") (pin "2") (pinfunction "5V_2") (pintype "passive"))
      (node (ref "PI") (pin "4") (pinfunction "5V_4") (pintype "passive"))
      (node (ref "R19") (pin "1") (pinfunction "1_1") (pintype "passive"))
      (node (ref "R20") (pin "1") (pinfunction "1_1") (pintype "passive"))
      (node (ref "U1") (pin "13") (pinfunction "VIN_13") (pintype "passive"))
      (node (ref "VR1") (pin "4") (pinfunction "Vout_4") (pintype "passive"))
      (node (ref "VR1") (pin "5") (pinfunction "Sense_5") (pintype "passive"))
      (node (ref "VR2") (pin "1") (pinfunction "1_1") (pintype "passive"))
    )
    (net (code "68") (name "Vbat") (class "Default")
      (node (ref "D2") (pin "1") (pinfunction "1_1") (pintype "power_in"))
      (node (ref "P1") (pin "2") (pinfunction "+ve_2") (pintype "passive"))
      (node (ref "U4") (pin "A6") (pinfunction "BAT_A6") (pintype "power_in"))
      (node (ref "U4") (pin "A7") (pinfunction "BAT_A7") (pintype "power_in"))
      (node (ref "U4") (pin "B6") (pinfunction "BAT_B6") (pintype "power_in"))
      (node (ref "U4") (pin "B7") (pinfunction "BAT_B7") (pintype "power_in"))
      (node (ref "U4") (pin "C6") (pinfunction "BAT_C6") (pintype "power_in"))
      (node (ref "U4") (pin "C7") (pinfunction "BAT_C7") (pintype "power_in"))
      (node (ref "U4") (pin "D6") (pinfunction "BAT_D6") (pintype "power_in"))
      (node (ref "U4") (pin "D7") (pinfunction "BAT_D7") (pintype "power_in"))
      (node (ref "U4") (pin "E6") (pinfunction "BAT_E6") (pintype "power_in"))
      (node (ref "U4") (pin "E7") (pinfunction "BAT_E7") (pintype "power_in"))
      (node (ref "U4") (pin "F6") (pinfunction "BAT_F6") (pintype "power_in"))
      (node (ref "U4") (pin "F7") (pinfunction "BAT_F7") (pintype "power_in"))
      (node (ref "U4") (pin "G7") (pinfunction "BIAS_G7") (pintype "power_in"))
    )
    (net (code "69") (name "Vdc") (class "Default")
      (node (ref "D1") (pin "1") (pinfunction "1_1") (pintype "power_in"))
      (node (ref "P2") (pin "1") (pinfunction "1_1") (pintype "passive"))
      (node (ref "U4") (pin "K5") (pinfunction "VINA_K5") (pintype "power_in"))
      (node (ref "U4") (pin "K6") (pinfunction "RUN_K6") (pintype "input"))
      (node (ref "U4") (pin "L5") (pinfunction "VINA_L5") (pintype "power_in"))
      (node (ref "U4") (pin "L6") (pinfunction "VINA_L6") (pintype "power_in"))
      (node (ref "U4") (pin "L7") (pinfunction "VINA_L7") (pintype "power_in"))
    )
    (net (code "70") (name "Vsys") (class "Default")
      (node (ref "D1") (pin "2") (pinfunction "2_2") (pintype "power_in"))
      (node (ref "D2") (pin "2") (pinfunction "2_2") (pintype "power_in"))
      (node (ref "SW1") (pin "2") (pinfunction "2_2") (pintype "passive"))
    )
    (net (code "71") (name "unconnected-(PI-3V3-Pad1)") (class "Default")
      (node (ref "PI") (pin "1") (pinfunction "3V3_1") (pintype "passive"))
    )
    (net (code "72") (name "unconnected-(PI-P4-Pad7)") (class "Default")
      (node (ref "PI") (pin "7") (pinfunction "P4_7") (pintype "passive"))
    )
    (net (code "73") (name "unconnected-(PI-P6-Pad31)") (class "Default")
      (node (ref "PI") (pin "31") (pinfunction "P6_31") (pintype "passive"))
    )
    (net (code "74") (name "unconnected-(PI-P12-Pad32)") (class "Default")
      (node (ref "PI") (pin "32") (pinfunction "P12_32") (pintype "passive"))
    )
    (net (code "75") (name "unconnected-(PI-P17-Pad11)") (class "Default")
      (node (ref "PI") (pin "11") (pinfunction "P17_11") (pintype "passive"))
    )
    (net (code "76") (name "unconnected-(PI-P18-Pad12)") (class "Default")
      (node (ref "PI") (pin "12") (pinfunction "P18_12") (pintype "passive"))
    )
    (net (code "77") (name "unconnected-(PI-P21-Pad40)") (class "Default")
      (node (ref "PI") (pin "40") (pinfunction "P21_40") (pintype "passive"))
    )
    (net (code "78") (name "unconnected-(PI-P23-Pad16)") (class "Default")
      (node (ref "PI") (pin "16") (pinfunction "P23_16") (pintype "passive"))
    )
    (net (code "79") (name "unconnected-(PI-P25-Pad22)") (class "Default")
      (node (ref "PI") (pin "22") (pinfunction "P25_22") (pintype "passive"))
    )
    (net (code "80") (name "unconnected-(PI-P27-Pad13)") (class "Default")
      (node (ref "PI") (pin "13") (pinfunction "P27_13") (pintype "passive"))
    )
    (net (code "81") (name "unconnected-(PI-SC-Pad28)") (class "Default")
      (node (ref "PI") (pin "28") (pinfunction "SC_28") (pintype "passive"))
    )
    (net (code "82") (name "unconnected-(PI-SD-Pad27)") (class "Default")
      (node (ref "PI") (pin "27") (pinfunction "SD_27") (pintype "passive"))
    )
    (net (code "83") (name "unconnected-(SW1-Pad3)") (class "Default")
      (node (ref "SW1") (pin "3") (pinfunction "3_3") (pintype "passive"))
    )
    (net (code "84") (name "unconnected-(U1-VMM-Pad8)") (class "Default")
      (node (ref "U1") (pin "8") (pinfunction "VMM_8") (pintype "passive+no_connect"))
    )
    (net (code "85") (name "unconnected-(U4A-NTC-PadH6)") (class "Default")
      (node (ref "U4") (pin "H6") (pinfunction "NTC_H6") (pintype "input+no_connect"))
    )
    (net (code "86") (name "unconnected-(VR1-Seq-Pad9)") (class "Default")
      (node (ref "VR1") (pin "9") (pinfunction "Seq_9") (pintype "passive+no_connect"))
    )
  )
)
